# MicroSDCard.net
KiCad netlist of a schematic drawn in Altium Designer
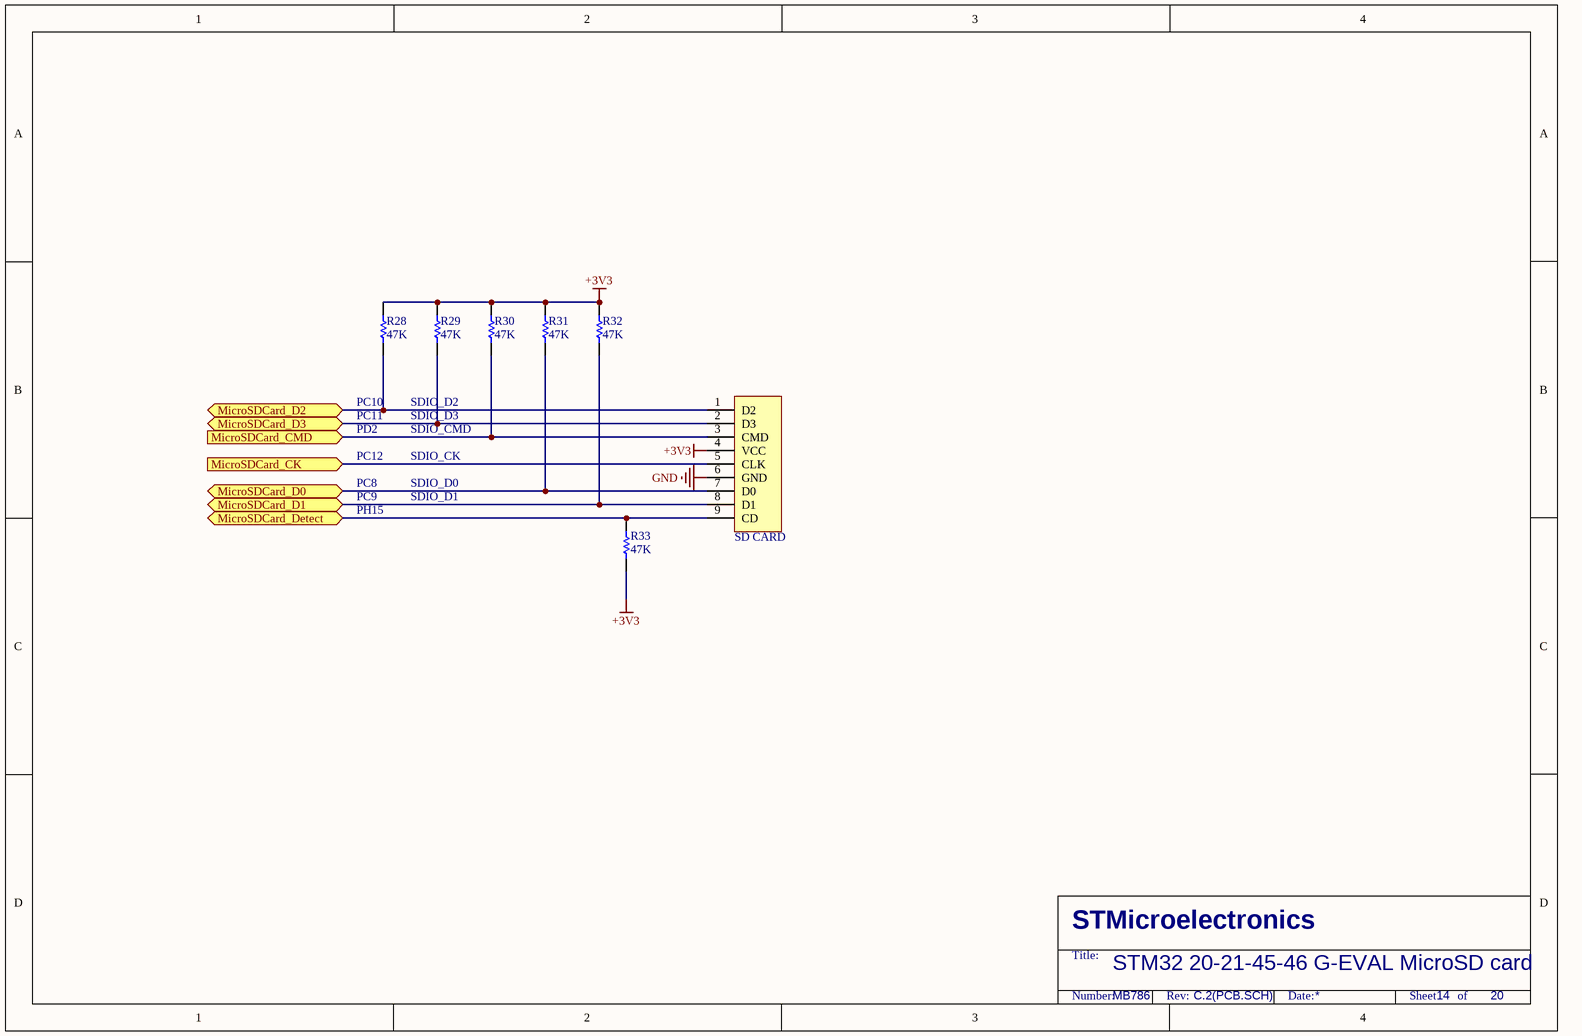
[diagram p0: MicroSDCard.SchDoc]

(export (version "E")
  (design (tool "Eeschema 10.0.6"))
  (components
    (comp (ref "R28")
      (value "47K")
      (footprint "0603_R")
      (description "Resistor")
      (fields (field (name "PUBLISHER") "Altium Limited"))
      (libsource (lib "Miscellaneous Devices") (part "Res1"))
    )
    (comp (ref "R29")
      (value "47K")
      (footprint "0603_R")
      (description "Resistor")
      (fields (field (name "PUBLISHER") "Altium Limited"))
      (libsource (lib "Miscellaneous Devices") (part "Res1"))
    )
    (comp (ref "R30")
      (value "47K")
      (footprint "0603_R")
      (description "Resistor")
      (fields (field (name "PUBLISHER") "Altium Limited"))
      (libsource (lib "Miscellaneous Devices") (part "Res1"))
    )
    (comp (ref "R31")
      (value "47K")
      (footprint "0603_R")
      (description "Resistor")
      (fields (field (name "PUBLISHER") "Altium Limited"))
      (libsource (lib "Miscellaneous Devices") (part "Res1"))
    )
    (comp (ref "R32")
      (value "47K")
      (footprint "0603_R")
      (description "Resistor")
      (fields (field (name "PUBLISHER") "Altium Limited"))
      (libsource (lib "Miscellaneous Devices") (part "Res1"))
    )
    (comp (ref "R33")
      (value "47K")
      (footprint "0603_R")
      (description "Resistor")
      (fields (field (name "PUBLISHER") "Altium Limited"))
      (libsource (lib "Miscellaneous Devices") (part "Res1"))
    )
    (comp (ref "SD CARD")
      (value "SD_Card_TF")
      (footprint "PCB_SDCard:SD_Card_TF")
      (description "SD")
      (libsource (lib "SCH_SDCard") (part "SD_Card_TF"))
    )
  )
  (nets
    (net (code "1") (name "+3V3") (class "Default")
      (node (ref "R28") (pin "1") (pinfunction "1_1") (pintype "passive"))
      (node (ref "R29") (pin "1") (pinfunction "1_1") (pintype "passive"))
      (node (ref "R30") (pin "1") (pinfunction "1_1") (pintype "passive"))
      (node (ref "R31") (pin "1") (pinfunction "1_1") (pintype "passive"))
      (node (ref "R32") (pin "1") (pinfunction "1_1") (pintype "passive"))
      (node (ref "R33") (pin "2") (pinfunction "2_2") (pintype "passive"))
      (node (ref "SD CARD") (pin "4") (pinfunction "VCC_4") (pintype "passive"))
    )
    (net (code "2") (name "/MicroSDCard_CK") (class "Default")
      (node (ref "SD CARD") (pin "5") (pinfunction "CLK_5") (pintype "passive"))
    )
    (net (code "3") (name "/MicroSDCard_CMD") (class "Default")
      (node (ref "R30") (pin "2") (pinfunction "2_2") (pintype "passive"))
      (node (ref "SD CARD") (pin "3") (pinfunction "CMD_3") (pintype "passive"))
    )
    (net (code "4") (name "/MicroSDCard_D0") (class "Default")
      (node (ref "R31") (pin "2") (pinfunction "2_2") (pintype "passive"))
      (node (ref "SD CARD") (pin "7") (pinfunction "D0_7") (pintype "passive"))
    )
    (net (code "5") (name "/MicroSDCard_D1") (class "Default")
      (node (ref "R32") (pin "2") (pinfunction "2_2") (pintype "passive"))
      (node (ref "SD CARD") (pin "8") (pinfunction "D1_8") (pintype "passive"))
    )
    (net (code "6") (name "/MicroSDCard_D2") (class "Default")
      (node (ref "R28") (pin "2") (pinfunction "2_2") (pintype "passive"))
      (node (ref "SD CARD") (pin "1") (pinfunction "D2_1") (pintype "passive"))
    )
    (net (code "7") (name "/MicroSDCard_D3") (class "Default")
      (node (ref "R29") (pin "2") (pinfunction "2_2") (pintype "passive"))
      (node (ref "SD CARD") (pin "2") (pinfunction "D3_2") (pintype "passive"))
    )
    (net (code "8") (name "/MicroSDCard_Detect") (class "Default")
      (node (ref "R33") (pin "1") (pinfunction "1_1") (pintype "passive"))
      (node (ref "SD CARD") (pin "9") (pinfunction "CD_9") (pintype "passive"))
    )
    (net (code "9") (name "GND") (class "Default")
      (node (ref "SD CARD") (pin "6") (pinfunction "GND_6") (pintype "passive"))
    )
  )
)
